# 24TFTSPI240x320.net
KiCad netlist of a schematic drawn in Altium Designer
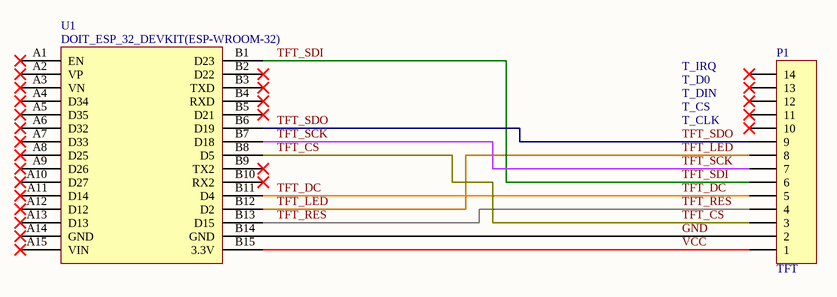
[diagram p0: 24TFTSPI240x320.SchDoc]

(export (version "E")
  (design (tool "Eeschema 10.0.6"))
  (components
    (comp (ref "P1")
      (value "TFT")
      (footprint "HDR1X14")
      (description "Header, 14-Pin")
      (fields (field (name "PUBLISHER") "Altium Limited"))
      (libsource (lib "Miscellaneous Connectors") (part "Header 14"))
    )
    (comp (ref "U1")
      (value "DOIT_ESP_32_DEVKIT(ESP-WROOM-32)")
      (libsource (lib "yoRadio_mod_sch") (part "DOIT_ESP_32_DEVKIT"))
    )
  )
  (nets
    (net (code "1") (name "/GND") (class "Default")
      (node (ref "P1") (pin "2") (pinfunction "2_2") (pintype "passive"))
      (node (ref "U1") (pin "B14") (pinfunction "GND_B14") (pintype "passive"))
    )
    (net (code "2") (name "/TFT_CS") (class "Default")
      (node (ref "P1") (pin "3") (pinfunction "3_3") (pintype "passive"))
      (node (ref "U1") (pin "B8") (pinfunction "D5_B8") (pintype "passive"))
    )
    (net (code "3") (name "/TFT_DC") (class "Default")
      (node (ref "P1") (pin "5") (pinfunction "5_5") (pintype "passive"))
      (node (ref "U1") (pin "B11") (pinfunction "D4_B11") (pintype "passive"))
    )
    (net (code "4") (name "/TFT_LED") (class "Default")
      (node (ref "P1") (pin "8") (pinfunction "8_8") (pintype "passive"))
      (node (ref "U1") (pin "B12") (pinfunction "D2_B12") (pintype "passive"))
    )
    (net (code "5") (name "/TFT_RES") (class "Default")
      (node (ref "P1") (pin "4") (pinfunction "4_4") (pintype "passive"))
      (node (ref "U1") (pin "B13") (pinfunction "D15_B13") (pintype "passive"))
    )
    (net (code "6") (name "/TFT_SCK") (class "Default")
      (node (ref "P1") (pin "7") (pinfunction "7_7") (pintype "passive"))
      (node (ref "U1") (pin "B7") (pinfunction "D18_B7") (pintype "passive"))
    )
    (net (code "7") (name "/TFT_SDI") (class "Default")
      (node (ref "P1") (pin "6") (pinfunction "6_6") (pintype "passive"))
      (node (ref "U1") (pin "B1") (pinfunction "D23_B1") (pintype "passive"))
    )
    (net (code "8") (name "/TFT_SDO") (class "Default")
      (node (ref "P1") (pin "9") (pinfunction "9_9") (pintype "passive"))
      (node (ref "U1") (pin "B6") (pinfunction "D19_B6") (pintype "passive"))
    )
    (net (code "9") (name "/VCC") (class "Default")
      (node (ref "P1") (pin "1") (pinfunction "1_1") (pintype "passive"))
      (node (ref "U1") (pin "B15") (pinfunction "3.3V_B15") (pintype "passive"))
    )
    (net (code "10") (name "unconnected-(P1-Pad10)") (class "Default")
      (node (ref "P1") (pin "10") (pinfunction "10_10") (pintype "passive+no_connect"))
    )
    (net (code "11") (name "unconnected-(P1-Pad11)") (class "Default")
      (node (ref "P1") (pin "11") (pinfunction "11_11") (pintype "passive+no_connect"))
    )
    (net (code "12") (name "unconnected-(P1-Pad12)") (class "Default")
      (node (ref "P1") (pin "12") (pinfunction "12_12") (pintype "passive+no_connect"))
    )
    (net (code "13") (name "unconnected-(P1-Pad13)") (class "Default")
      (node (ref "P1") (pin "13") (pinfunction "13_13") (pintype "passive+no_connect"))
    )
    (net (code "14") (name "unconnected-(P1-Pad14)") (class "Default")
      (node (ref "P1") (pin "14") (pinfunction "14_14") (pintype "passive+no_connect"))
    )
    (net (code "15") (name "unconnected-(U1-D12-PadA12)") (class "Default")
      (node (ref "U1") (pin "A12") (pinfunction "D12_A12") (pintype "passive+no_connect"))
    )
    (net (code "16") (name "unconnected-(U1-D13-PadA13)") (class "Default")
      (node (ref "U1") (pin "A13") (pinfunction "D13_A13") (pintype "passive+no_connect"))
    )
    (net (code "17") (name "unconnected-(U1-D14-PadA11)") (class "Default")
      (node (ref "U1") (pin "A11") (pinfunction "D14_A11") (pintype "passive+no_connect"))
    )
    (net (code "18") (name "unconnected-(U1-D21-PadB5)") (class "Default")
      (node (ref "U1") (pin "B5") (pinfunction "D21_B5") (pintype "passive+no_connect"))
    )
    (net (code "19") (name "unconnected-(U1-D22-PadB2)") (class "Default")
      (node (ref "U1") (pin "B2") (pinfunction "D22_B2") (pintype "passive+no_connect"))
    )
    (net (code "20") (name "unconnected-(U1-D25-PadA8)") (class "Default")
      (node (ref "U1") (pin "A8") (pinfunction "D25_A8") (pintype "passive+no_connect"))
    )
    (net (code "21") (name "unconnected-(U1-D26-PadA9)") (class "Default")
      (node (ref "U1") (pin "A9") (pinfunction "D26_A9") (pintype "passive+no_connect"))
    )
    (net (code "22") (name "unconnected-(U1-D27-PadA10)") (class "Default")
      (node (ref "U1") (pin "A10") (pinfunction "D27_A10") (pintype "passive+no_connect"))
    )
    (net (code "23") (name "unconnected-(U1-D32-PadA6)") (class "Default")
      (node (ref "U1") (pin "A6") (pinfunction "D32_A6") (pintype "passive+no_connect"))
    )
    (net (code "24") (name "unconnected-(U1-D33-PadA7)") (class "Default")
      (node (ref "U1") (pin "A7") (pinfunction "D33_A7") (pintype "passive+no_connect"))
    )
    (net (code "25") (name "unconnected-(U1-D34-PadA4)") (class "Default")
      (node (ref "U1") (pin "A4") (pinfunction "D34_A4") (pintype "passive+no_connect"))
    )
    (net (code "26") (name "unconnected-(U1-D35-PadA5)") (class "Default")
      (node (ref "U1") (pin "A5") (pinfunction "D35_A5") (pintype "passive+no_connect"))
    )
    (net (code "27") (name "unconnected-(U1-EN-PadA1)") (class "Default")
      (node (ref "U1") (pin "A1") (pinfunction "EN_A1") (pintype "passive+no_connect"))
    )
    (net (code "28") (name "unconnected-(U1-GND-PadA14)") (class "Default")
      (node (ref "U1") (pin "A14") (pinfunction "GND_A14") (pintype "passive+no_connect"))
    )
    (net (code "29") (name "unconnected-(U1-RX2-PadB10)") (class "Default")
      (node (ref "U1") (pin "B10") (pinfunction "RX2_B10") (pintype "passive+no_connect"))
    )
    (net (code "30") (name "unconnected-(U1-RXD-PadB4)") (class "Default")
      (node (ref "U1") (pin "B4") (pinfunction "RXD_B4") (pintype "passive+no_connect"))
    )
    (net (code "31") (name "unconnected-(U1-TX2-PadB9)") (class "Default")
      (node (ref "U1") (pin "B9") (pinfunction "TX2_B9") (pintype "passive+no_connect"))
    )
    (net (code "32") (name "unconnected-(U1-TXD-PadB3)") (class "Default")
      (node (ref "U1") (pin "B3") (pinfunction "TXD_B3") (pintype "passive+no_connect"))
    )
    (net (code "33") (name "unconnected-(U1-VIN-PadA15)") (class "Default")
      (node (ref "U1") (pin "A15") (pinfunction "VIN_A15") (pintype "passive+no_connect"))
    )
    (net (code "34") (name "unconnected-(U1-VN-PadA3)") (class "Default")
      (node (ref "U1") (pin "A3") (pinfunction "VN_A3") (pintype "passive+no_connect"))
    )
    (net (code "35") (name "unconnected-(U1-VP-PadA2)") (class "Default")
      (node (ref "U1") (pin "A2") (pinfunction "VP_A2") (pintype "passive+no_connect"))
    )
  )
)
